# TR.net
KiCad netlist of a schematic drawn in Altium Designer
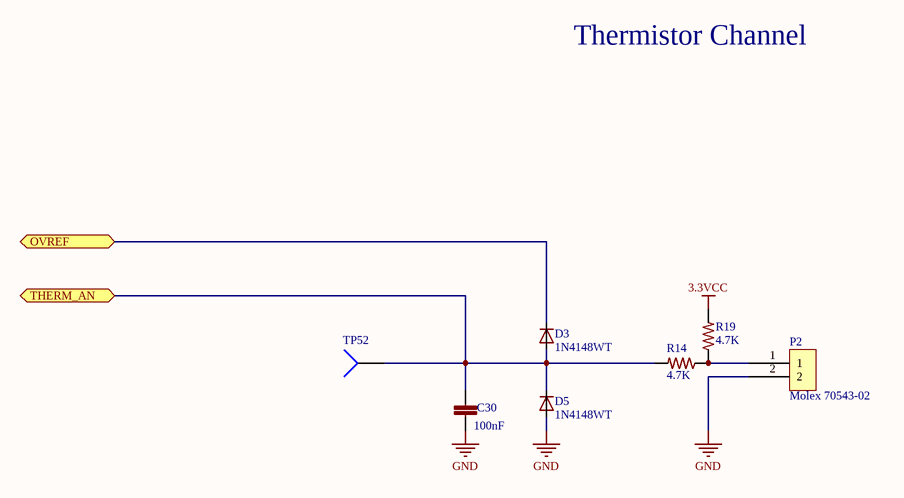
[diagram p0: TR.SchDoc]

(export (version "E")
  (design (tool "Eeschema 10.0.6"))
  (components
    (comp (ref "C30")
      (value "100nF")
      (footprint "C0402")
      (description "CAP CER 0402 100nF 16V 10% X7R")
      (fields
        (field (name "MANUFACTURERPARTNUMBER") "GRM155R71C104KA88D")
        (field (name "PUBLISHER") "UltiMachine")
      )
      (libsource (lib "3Delight") (part "GRM155R71C104KA88D"))
    )
    (comp (ref "D3")
      (value "1N4148WT")
      (footprint "SOD523")
      (description "DIODE SOD523")
      (fields (field (name "PUBLISHER") "UltiMachine"))
      (libsource (lib "3Delight") (part "1N4148WT"))
    )
    (comp (ref "D5")
      (value "1N4148WT")
      (footprint "SOD523")
      (description "DIODE SOD523")
      (fields (field (name "PUBLISHER") "UltiMachine"))
      (libsource (lib "3Delight") (part "1N4148WT"))
    )
    (comp (ref "P2")
      (value "Molex 70543-02")
      (footprint "70543-02")
      (libsource (lib "ZMBo Schematic Library") (part "Molex 70543-02"))
    )
    (comp (ref "R14")
      (value "4.7K")
      (footprint "R0603")
      (description "RES 0603 4.7K 100mW 1%")
      (fields (field (name "MANUFACTURERPARTNUMBER") "ERJ3EKF4701V") (field (name "PUBLISHER") "UltiMachine"))
      (libsource (lib "3Delight") (part "ERJ3EKF4701V"))
    )
    (comp (ref "R19")
      (value "4.7K")
      (footprint "R0603")
      (description "RES 0603 4.7K 100mW 1%")
      (fields (field (name "MANUFACTURERPARTNUMBER") "ERJ3EKF4701V") (field (name "PUBLISHER") "UltiMachine"))
      (libsource (lib "3Delight") (part "ERJ3EKF4701V"))
    )
    (comp (ref "TP52")
      (value "TP4")
      (footprint "TP-2")
      (description "Socket")
      (fields (field (name "PUBLISHER") "Altium Limited"))
      (libsource (lib "ZMBo Schematic Library") (part "Socket"))
    )
  )
  (nets
    (net (code "1") (name "/OVREF") (class "Default")
      (node (ref "D3") (pin "C") (pinfunction "C_C") (pintype "passive"))
    )
    (net (code "2") (name "/THERM_AN") (class "Default")
      (node (ref "C30") (pin "1") (pinfunction "1_1") (pintype "passive"))
      (node (ref "D3") (pin "A") (pinfunction "A_A") (pintype "passive"))
      (node (ref "D5") (pin "C") (pinfunction "C_C") (pintype "passive"))
      (node (ref "R14") (pin "2") (pinfunction "2_2") (pintype "passive"))
      (node (ref "TP52") (pin "1") (pinfunction "1_1") (pintype "passive"))
    )
    (net (code "3") (name "3.3VCC") (class "Default")
      (node (ref "R19") (pin "2") (pinfunction "2_2") (pintype "passive"))
    )
    (net (code "4") (name "GND") (class "Default")
      (node (ref "C30") (pin "2") (pinfunction "2_2") (pintype "passive"))
      (node (ref "D5") (pin "A") (pinfunction "A_A") (pintype "passive"))
      (node (ref "P2") (pin "2") (pinfunction "2_2") (pintype "passive"))
    )
    (net (code "5") (name "Net-(P2-Pad1)") (class "Default")
      (node (ref "P2") (pin "1") (pinfunction "1_1") (pintype "passive"))
      (node (ref "R14") (pin "1") (pinfunction "1_1") (pintype "passive"))
      (node (ref "R19") (pin "1") (pinfunction "1_1") (pintype "passive"))
    )
  )
)
